# PowerBoardConnector.net
KiCad netlist of a schematic drawn in Altium Designer
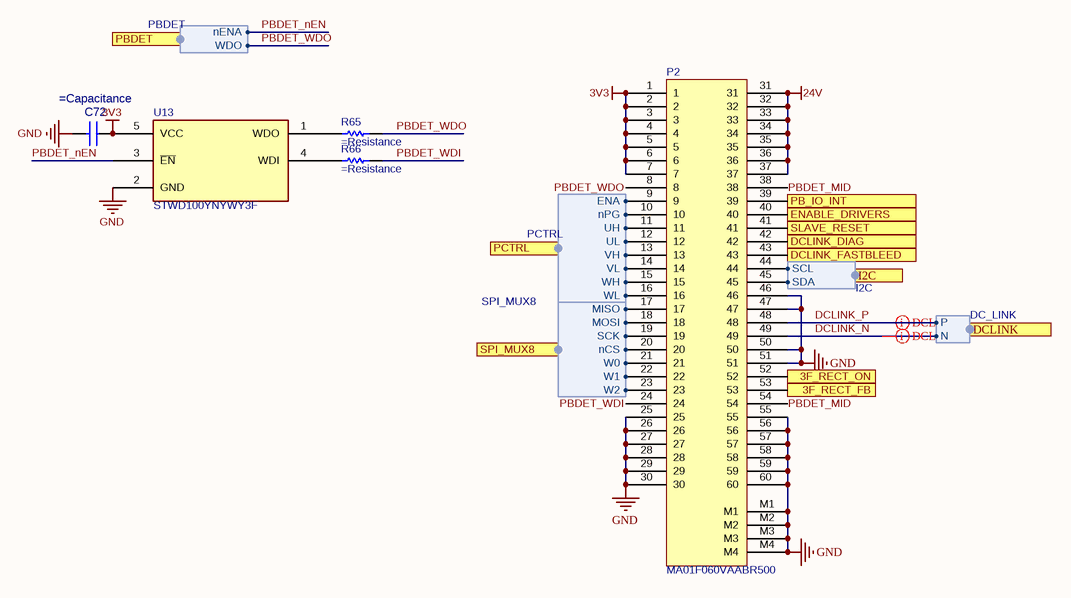
[diagram p0: PowerBoardConnector.SchDoc]

(export (version "E")
  (design (tool "Eeschema 10.0.6"))
  (components
    (comp (ref "C72")
      (value "~")
      (footprint "C0402")
      (description "CAP CER 0.1UF 50V X7R 0402")
      (fields
        (field (name "MANUFACTURER") "Walsin Technologies")
        (field (name "MANUFACTURER PART NUMBER") "0402B104K500CT")
      )
      (libsource (lib "Capacitors") (part "CAP0402-0.1uF-50V"))
    )
    (comp (ref "P2")
      (value "MA01F060VAABR500")
      (footprint "MA01F060VAABR500")
      (libsource (lib "Connectors") (part "MA01F060VAABR500"))
    )
    (comp (ref "R65")
      (value "~")
      (footprint "R0402")
      (description "Res Thick Film 0402 1K Ohm 1% 0.063W(1/16W) ±50ppm/C Pad SMD Automotive T/R")
      (fields
        (field (name "MANUFACTURER") "Vishay")
        (field (name "MANUFACTURER PART NUMBER") "CRCW04021K00FHEDP")
      )
      (libsource (lib "Resistors") (part "RES0402-1k-1%"))
    )
    (comp (ref "R66")
      (value "~")
      (footprint "R0402")
      (description "Res Thick Film 0402 1K Ohm 1% 0.063W(1/16W) ±50ppm/C Pad SMD Automotive T/R")
      (fields
        (field (name "MANUFACTURER") "Vishay")
        (field (name "MANUFACTURER PART NUMBER") "CRCW04021K00FHEDP")
      )
      (libsource (lib "Resistors") (part "RES0402-1k-1%"))
    )
    (comp (ref "U13")
      (value "STWD100YNYWY3F")
      (footprint "SOT-23-5")
      (description "Processor Supervisor 1 Open Drain/Push-Pull Automotive AEC-Q100 5-Pin SOT-23 T/R")
      (fields (field (name "MANUFACTURER") "STMicroelectronics"))
      (libsource (lib "IC") (part "STWD100YNYWY3F"))
    )
  )
  (nets
    (net (code "6") (name "/3F_RECT_FB") (class "Default")
      (node (ref "P2") (pin "53") (pinfunction "53_53") (pintype "passive"))
    )
    (net (code "7") (name "/3F_RECT_ON") (class "Default")
      (node (ref "P2") (pin "52") (pinfunction "52_52") (pintype "passive"))
    )
    (net (code "8") (name "/DCLINK_DIAG") (class "Default")
      (node (ref "P2") (pin "42") (pinfunction "42_42") (pintype "passive"))
    )
    (net (code "9") (name "/DCLINK_FASTBLEED") (class "Default")
      (node (ref "P2") (pin "43") (pinfunction "43_43") (pintype "passive"))
    )
    (net (code "10") (name "/DCLINK_N") (class "Default")
      (node (ref "P2") (pin "49") (pinfunction "49_49") (pintype "passive"))
    )
    (net (code "11") (name "/DCLINK_P") (class "Default")
      (node (ref "P2") (pin "48") (pinfunction "48_48") (pintype "passive"))
    )
    (net (code "12") (name "/ENA") (class "Default")
      (node (ref "P2") (pin "9") (pinfunction "9_9") (pintype "passive"))
    )
    (net (code "13") (name "/ENABLE_DRIVERS") (class "Default")
      (node (ref "P2") (pin "40") (pinfunction "40_40") (pintype "passive"))
    )
    (net (code "14") (name "/MISO") (class "Default")
      (node (ref "P2") (pin "17") (pinfunction "17_17") (pintype "passive"))
    )
    (net (code "15") (name "/MOSI") (class "Default")
      (node (ref "P2") (pin "18") (pinfunction "18_18") (pintype "passive"))
    )
    (net (code "16") (name "/PBDET_MID") (class "Default")
      (node (ref "P2") (pin "38") (pinfunction "38_38") (pintype "passive"))
      (node (ref "P2") (pin "54") (pinfunction "54_54") (pintype "passive"))
    )
    (net (code "17") (name "/PBDET_WDI") (class "Default")
      (node (ref "P2") (pin "24") (pinfunction "24_24") (pintype "passive"))
      (node (ref "R66") (pin "2") (pinfunction "2_2") (pintype "passive"))
    )
    (net (code "18") (name "/PBDET_WDO") (class "Default")
      (node (ref "P2") (pin "8") (pinfunction "8_8") (pintype "passive"))
      (node (ref "R65") (pin "2") (pinfunction "2_2") (pintype "passive"))
    )
    (net (code "19") (name "/PBDET_nEN") (class "Default")
      (node (ref "U13") (pin "3") (pinfunction "~{EN}_3") (pintype "passive"))
    )
    (net (code "20") (name "/PB_IO_INT") (class "Default")
      (node (ref "P2") (pin "39") (pinfunction "39_39") (pintype "passive"))
    )
    (net (code "21") (name "/SCK") (class "Default")
      (node (ref "P2") (pin "19") (pinfunction "19_19") (pintype "passive"))
    )
    (net (code "22") (name "/SCL") (class "Default")
      (node (ref "P2") (pin "44") (pinfunction "44_44") (pintype "passive"))
    )
    (net (code "23") (name "/SDA") (class "Default")
      (node (ref "P2") (pin "45") (pinfunction "45_45") (pintype "passive"))
    )
    (net (code "24") (name "/SLAVE_RESET") (class "Default")
      (node (ref "P2") (pin "41") (pinfunction "41_41") (pintype "passive"))
    )
    (net (code "25") (name "/UH") (class "Default")
      (node (ref "P2") (pin "11") (pinfunction "11_11") (pintype "passive"))
    )
    (net (code "26") (name "/UL") (class "Default")
      (node (ref "P2") (pin "12") (pinfunction "12_12") (pintype "passive"))
    )
    (net (code "27") (name "/VH") (class "Default")
      (node (ref "P2") (pin "13") (pinfunction "13_13") (pintype "passive"))
    )
    (net (code "28") (name "/VL") (class "Default")
      (node (ref "P2") (pin "14") (pinfunction "14_14") (pintype "passive"))
    )
    (net (code "29") (name "/W0") (class "Default")
      (node (ref "P2") (pin "21") (pinfunction "21_21") (pintype "passive"))
    )
    (net (code "30") (name "/W1") (class "Default")
      (node (ref "P2") (pin "22") (pinfunction "22_22") (pintype "passive"))
    )
    (net (code "31") (name "/W2") (class "Default")
      (node (ref "P2") (pin "23") (pinfunction "23_23") (pintype "passive"))
    )
    (net (code "32") (name "/WH") (class "Default")
      (node (ref "P2") (pin "15") (pinfunction "15_15") (pintype "passive"))
    )
    (net (code "33") (name "/WL") (class "Default")
      (node (ref "P2") (pin "16") (pinfunction "16_16") (pintype "passive"))
    )
    (net (code "34") (name "/nCS") (class "Default")
      (node (ref "P2") (pin "20") (pinfunction "20_20") (pintype "passive"))
    )
    (net (code "35") (name "/nPG") (class "Default")
      (node (ref "P2") (pin "10") (pinfunction "10_10") (pintype "passive"))
    )
    (net (code "41") (name "3V3") (class "Default")
      (node (ref "C72") (pin "1") (pinfunction "1_1") (pintype "passive"))
      (node (ref "P2") (pin "1") (pinfunction "1_1") (pintype "passive"))
      (node (ref "P2") (pin "2") (pinfunction "2_2") (pintype "passive"))
      (node (ref "P2") (pin "3") (pinfunction "3_3") (pintype "passive"))
      (node (ref "P2") (pin "4") (pinfunction "4_4") (pintype "passive"))
      (node (ref "P2") (pin "5") (pinfunction "5_5") (pintype "passive"))
      (node (ref "P2") (pin "6") (pinfunction "6_6") (pintype "passive"))
      (node (ref "P2") (pin "7") (pinfunction "7_7") (pintype "passive"))
      (node (ref "U13") (pin "5") (pinfunction "VCC_5") (pintype "passive"))
    )
    (net (code "42") (name "24V") (class "Default")
      (node (ref "P2") (pin "31") (pinfunction "31_31") (pintype "passive"))
      (node (ref "P2") (pin "32") (pinfunction "32_32") (pintype "passive"))
      (node (ref "P2") (pin "33") (pinfunction "33_33") (pintype "passive"))
      (node (ref "P2") (pin "34") (pinfunction "34_34") (pintype "passive"))
      (node (ref "P2") (pin "35") (pinfunction "35_35") (pintype "passive"))
      (node (ref "P2") (pin "36") (pinfunction "36_36") (pintype "passive"))
      (node (ref "P2") (pin "37") (pinfunction "37_37") (pintype "passive"))
    )
    (net (code "43") (name "GND") (class "Default")
      (node (ref "C72") (pin "2") (pinfunction "2_2") (pintype "passive"))
      (node (ref "P2") (pin "25") (pinfunction "25_25") (pintype "passive"))
      (node (ref "P2") (pin "26") (pinfunction "26_26") (pintype "passive"))
      (node (ref "P2") (pin "27") (pinfunction "27_27") (pintype "passive"))
      (node (ref "P2") (pin "28") (pinfunction "28_28") (pintype "passive"))
      (node (ref "P2") (pin "29") (pinfunction "29_29") (pintype "passive"))
      (node (ref "P2") (pin "30") (pinfunction "30_30") (pintype "passive"))
      (node (ref "P2") (pin "46") (pinfunction "46_46") (pintype "passive"))
      (node (ref "P2") (pin "47") (pinfunction "47_47") (pintype "passive"))
      (node (ref "P2") (pin "50") (pinfunction "50_50") (pintype "passive"))
      (node (ref "P2") (pin "51") (pinfunction "51_51") (pintype "passive"))
      (node (ref "P2") (pin "55") (pinfunction "55_55") (pintype "passive"))
      (node (ref "P2") (pin "56") (pinfunction "56_56") (pintype "passive"))
      (node (ref "P2") (pin "57") (pinfunction "57_57") (pintype "passive"))
      (node (ref "P2") (pin "58") (pinfunction "58_58") (pintype "passive"))
      (node (ref "P2") (pin "59") (pinfunction "59_59") (pintype "passive"))
      (node (ref "P2") (pin "60") (pinfunction "60_60") (pintype "passive"))
      (node (ref "P2") (pin "M1") (pinfunction "M1_M1") (pintype "passive"))
      (node (ref "P2") (pin "M2") (pinfunction "M2_M2") (pintype "passive"))
      (node (ref "P2") (pin "M3") (pinfunction "M3_M3") (pintype "passive"))
      (node (ref "P2") (pin "M4") (pinfunction "M4_M4") (pintype "passive"))
      (node (ref "U13") (pin "2") (pinfunction "GND_2") (pintype "passive"))
    )
    (net (code "44") (name "Net-(U13-WDI)") (class "Default")
      (node (ref "R66") (pin "1") (pinfunction "1_1") (pintype "passive"))
      (node (ref "U13") (pin "4") (pinfunction "WDI_4") (pintype "passive"))
    )
    (net (code "45") (name "Net-(U13-WDO)") (class "Default")
      (node (ref "R65") (pin "1") (pinfunction "1_1") (pintype "passive"))
      (node (ref "U13") (pin "1") (pinfunction "WDO_1") (pintype "passive"))
    )
  )
)
